# HV_Stage.net
KiCad netlist of a schematic drawn in Altium Designer
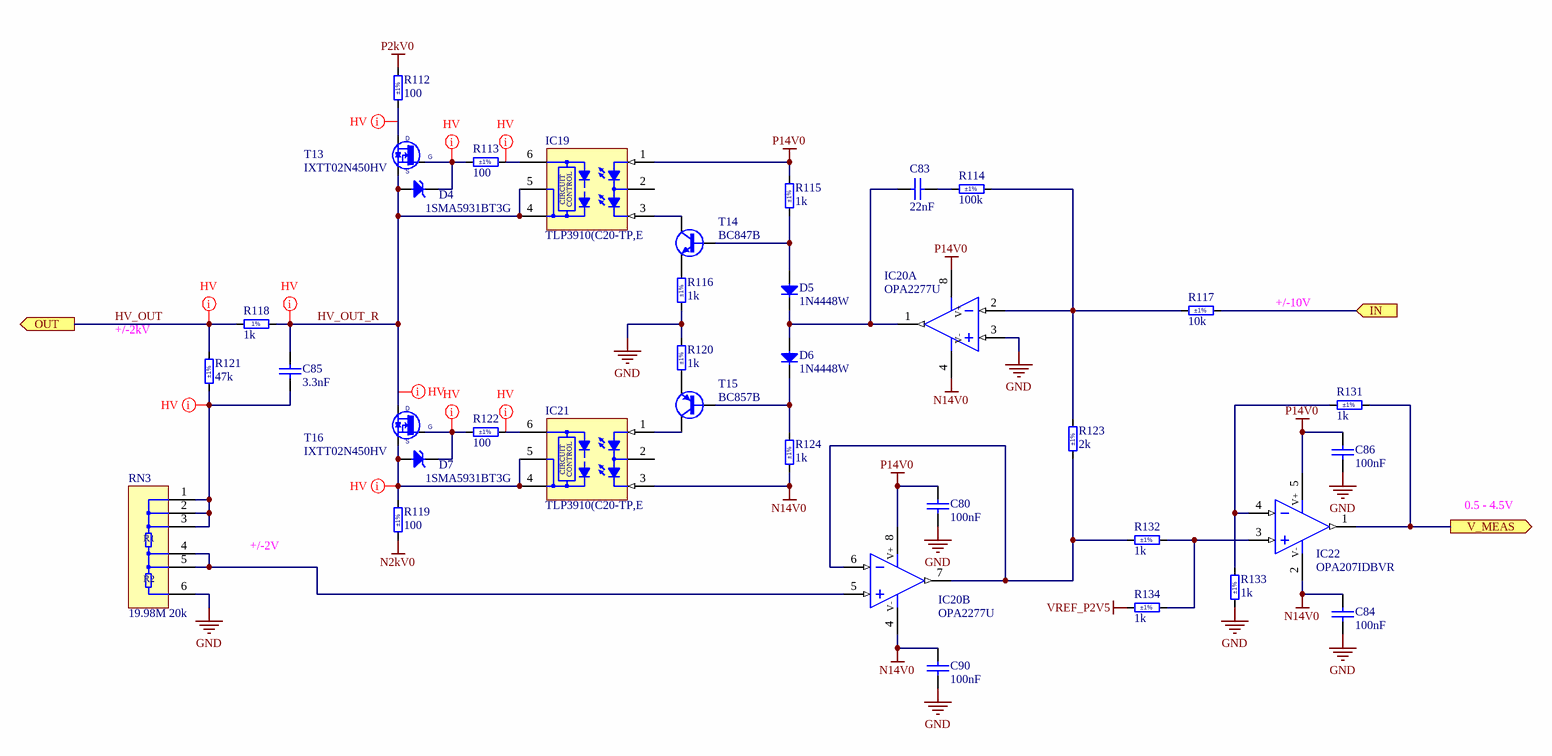
[diagram p0: HV_Stage.SchDoc]

(export (version "E")
  (design (tool "Eeschema 10.0.6"))
  (components
    (comp (ref "C80")
      (value "100nF")
      (footprint "CAPC1005X55N")
      (description "Non-polarised capacitor")
      (fields
        (field (name "PART NUMBER") "CC0402_100NF_50V_10%_X7R")
        (field (name "VOLTAGE") "50V")
        (field (name "AUTHOR") "CERN DEM MR")
      )
      (libsource (lib "Capacitors") (part "Capacitor - non polarized"))
    )
    (comp (ref "C83")
      (value "22nF")
      (footprint "CAPC1005X55N")
      (description "Non-polarised capacitor")
      (fields
        (field (name "PART NUMBER") "CC0402_22NF_50V_5%_X7R")
        (field (name "VOLTAGE") "50V")
        (field (name "AUTHOR") "CERN DEM BC")
      )
      (libsource (lib "Capacitors") (part "Capacitor - non polarized"))
    )
    (comp (ref "C84")
      (value "100nF")
      (footprint "CAPC1005X55N")
      (description "Non-polarised capacitor")
      (fields
        (field (name "PART NUMBER") "CC0402_100NF_50V_10%_X7R")
        (field (name "VOLTAGE") "50V")
        (field (name "AUTHOR") "CERN DEM MR")
      )
      (libsource (lib "Capacitors") (part "Capacitor - non polarized"))
    )
    (comp (ref "C85")
      (value "3.3nF")
      (footprint "CAPC1608X87N")
      (description "Non-polarised capacitor")
      (fields
        (field (name "PART NUMBER") "CC0603_3.3NF_100V_1%_C0G")
        (field (name "VOLTAGE") "100V")
        (field (name "AUTHOR") "CERN DEM HF")
      )
      (libsource (lib "Capacitors") (part "Capacitor - non polarized"))
    )
    (comp (ref "C86")
      (value "100nF")
      (footprint "CAPC1005X55N")
      (description "Non-polarised capacitor")
      (fields
        (field (name "PART NUMBER") "CC0402_100NF_50V_10%_X7R")
        (field (name "VOLTAGE") "50V")
        (field (name "AUTHOR") "CERN DEM MR")
      )
      (libsource (lib "Capacitors") (part "Capacitor - non polarized"))
    )
    (comp (ref "C90")
      (value "100nF")
      (footprint "CAPC1005X55N")
      (description "Non-polarised capacitor")
      (fields
        (field (name "PART NUMBER") "CC0402_100NF_50V_10%_X7R")
        (field (name "VOLTAGE") "50V")
        (field (name "AUTHOR") "CERN DEM MR")
      )
      (libsource (lib "Capacitors") (part "Capacitor - non polarized"))
    )
    (comp (ref "D4")
      (value "1SMA5931BT3G")
      (footprint "DIOM5226X220N")
      (description "Zener Diode")
      (fields
        (field (name "VOLTAGE") "18V")
        (field (name "POWER") "1.5W")
        (field (name "AUTHOR") "CERN DEM BC")
      )
      (libsource (lib "ICs And Semiconductors") (part "Diode Zener"))
    )
    (comp (ref "D5")
      (value "1N4448W")
      (footprint "SOD3715X135N")
      (description "Diode")
      (fields
        (field (name "VOLTAGE") "75V")
        (field (name "POWER") "150mA")
        (field (name "AUTHOR") "CERN DEM JLC")
      )
      (libsource (lib "ICs And Semiconductors") (part "Diode"))
    )
    (comp (ref "D6")
      (value "1N4448W")
      (footprint "SOD3715X135N")
      (description "Diode")
      (fields
        (field (name "VOLTAGE") "75V")
        (field (name "POWER") "150mA")
        (field (name "AUTHOR") "CERN DEM JLC")
      )
      (libsource (lib "ICs And Semiconductors") (part "Diode"))
    )
    (comp (ref "D7")
      (value "1SMA5931BT3G")
      (footprint "DIOM5226X220N")
      (description "Zener Diode")
      (fields
        (field (name "VOLTAGE") "18V")
        (field (name "POWER") "1.5W")
        (field (name "AUTHOR") "CERN DEM BC")
      )
      (libsource (lib "ICs And Semiconductors") (part "Diode Zener"))
    )
    (comp (ref "IC19")
      (value "TLP3910(C20-TP,E")
      (footprint "TOSHIBA_SOIC127P1000X220-6N")
      (description "Optoisolator Photovoltaic Output 5000Vrms 2 Channel")
      (fields (field (name "MANUFACTURER") "TOSHIBA") (field (name "AUTHOR") "CERN DEM HF"))
      (libsource (lib "ICs And Semiconductors") (part "TLP3910"))
    )
    (comp (ref "IC20")
      (value "OPA2277U")
      (footprint "SOIC127P600X175-8N")
      (description "Dual Operational Amplifier")
      (fields (field (name "MANUFACTURER") "TEXAS INSTRUMENTS") (field (name "AUTHOR") "CERN DEM BC"))
      (libsource (lib "ICs And Semiconductors") (part "Operational Amplifier x2 Type1"))
    )
    (comp (ref "IC21")
      (value "TLP3910(C20-TP,E")
      (footprint "TOSHIBA_SOIC127P1000X220-6N")
      (description "Optoisolator Photovoltaic Output 5000Vrms 2 Channel")
      (fields (field (name "MANUFACTURER") "TOSHIBA") (field (name "AUTHOR") "CERN DEM HF"))
      (libsource (lib "ICs And Semiconductors") (part "TLP3910"))
    )
    (comp (ref "IC22")
      (value "OPA207IDBVR")
      (footprint "SOT95P280X145-5N")
      (description "2.2nV/sqrt Hz, Low-Power, 36-V Operational Amplifier")
      (fields (field (name "MANUFACTURER") "TEXAS INSTRUMENTS"))
      (libsource (lib "Operational Amplifiers") (part "OPA207IDBVR"))
    )
    (comp (ref "R112")
      (value "100")
      (footprint "RESC2012X60N")
      (description "Resistor - 1%")
      (fields
        (field (name "TOLERANCE") "±1%")
        (field (name "PART NUMBER") "R0805_100R_1%_0.125W_100PPM")
        (field (name "POWER") "0.125W")
        (field (name "AUTHOR") "CERN DEM JLC")
      )
      (libsource (lib "Resistors") (part "Resistor - 1%"))
    )
    (comp (ref "R113")
      (value "100")
      (footprint "RESC2012X60N")
      (description "Resistor - 1%")
      (fields
        (field (name "TOLERANCE") "±1%")
        (field (name "PART NUMBER") "R0805_100R_1%_0.125W_100PPM")
        (field (name "POWER") "0.125W")
        (field (name "AUTHOR") "CERN DEM JLC")
      )
      (libsource (lib "Resistors") (part "Resistor - 1%"))
    )
    (comp (ref "R114")
      (value "100k")
      (footprint "RESC1005X40N")
      (description "Resistor - 1%")
      (fields
        (field (name "TOLERANCE") "±1%")
        (field (name "PART NUMBER") "R0402_100K_1%_0.0625W_100PPM")
        (field (name "POWER") "0.0625W")
        (field (name "AUTHOR") "CERN DEM JLC")
      )
      (libsource (lib "Resistors") (part "Resistor - 1%"))
    )
    (comp (ref "R115")
      (value "1k")
      (footprint "RESC1005X40N")
      (description "Resistor - 1%")
      (fields
        (field (name "TOLERANCE") "±1%")
        (field (name "PART NUMBER") "R0402_1K_1%_0.0625W_100PPM")
        (field (name "POWER") "0.0625W")
        (field (name "AUTHOR") "CERN DEM JLC")
      )
      (libsource (lib "Resistors") (part "Resistor - 1%"))
    )
    (comp (ref "R116")
      (value "1k")
      (footprint "RESC1005X40N")
      (description "Resistor - 1%")
      (fields
        (field (name "TOLERANCE") "±1%")
        (field (name "PART NUMBER") "R0402_1K_1%_0.0625W_100PPM")
        (field (name "POWER") "0.0625W")
        (field (name "AUTHOR") "CERN DEM JLC")
      )
      (libsource (lib "Resistors") (part "Resistor - 1%"))
    )
    (comp (ref "R117")
      (value "10k")
      (footprint "RESC1005X40N")
      (description "Resistor - 1%")
      (fields
        (field (name "TOLERANCE") "±1%")
        (field (name "PART NUMBER") "R0402_10K_1%_0.0625W_100PPM")
        (field (name "POWER") "0.0625W")
        (field (name "AUTHOR") "CERN DEM JLC")
      )
      (libsource (lib "Resistors") (part "Resistor - 1%"))
    )
    (comp (ref "R118")
      (value "1k")
      (footprint "RESC6331X70N")
      (description "CRMV2512AF 1K 1% 100 Ef E3")
      (fields
        (field (name "MANUFACTURER") "Vishay")
        (field (name "MANUFACTURER PART NUMBER") "CRMV2512AF1K00FKEF")
      )
      (libsource (lib "mb") (part "CRMV2512AF1K00FKEF"))
    )
    (comp (ref "R119")
      (value "100")
      (footprint "RESC2012X60N")
      (description "Resistor - 1%")
      (fields
        (field (name "TOLERANCE") "±1%")
        (field (name "PART NUMBER") "R0805_100R_1%_0.125W_100PPM")
        (field (name "POWER") "0.125W")
        (field (name "AUTHOR") "CERN DEM JLC")
      )
      (libsource (lib "Resistors") (part "Resistor - 1%"))
    )
    (comp (ref "R120")
      (value "1k")
      (footprint "RESC1005X40N")
      (description "Resistor - 1%")
      (fields
        (field (name "TOLERANCE") "±1%")
        (field (name "PART NUMBER") "R0402_1K_1%_0.0625W_100PPM")
        (field (name "POWER") "0.0625W")
        (field (name "AUTHOR") "CERN DEM JLC")
      )
      (libsource (lib "Resistors") (part "Resistor - 1%"))
    )
    (comp (ref "R121")
      (value "47k")
      (footprint "RESC2012X60N")
      (description "Resistor - 1%")
      (fields
        (field (name "TOLERANCE") "±1%")
        (field (name "PART NUMBER") "R0805_47K_1%_0.125W_100PPM")
        (field (name "POWER") "0.125W")
        (field (name "AUTHOR") "CERN DEM JLC")
      )
      (libsource (lib "Resistors") (part "Resistor - 1%"))
    )
    (comp (ref "R122")
      (value "100")
      (footprint "RESC2012X60N")
      (description "Resistor - 1%")
      (fields
        (field (name "TOLERANCE") "±1%")
        (field (name "PART NUMBER") "R0805_100R_1%_0.125W_100PPM")
        (field (name "POWER") "0.125W")
        (field (name "AUTHOR") "CERN DEM JLC")
      )
      (libsource (lib "Resistors") (part "Resistor - 1%"))
    )
    (comp (ref "R123")
      (value "2k")
      (footprint "RESC1005X40N")
      (description "Resistor - 1%")
      (fields
        (field (name "TOLERANCE") "±1%")
        (field (name "PART NUMBER") "R0402_2K_1%_0.0625W_100PPM")
        (field (name "POWER") "0.0625W")
        (field (name "AUTHOR") "CERN DEM JLC")
      )
      (libsource (lib "Resistors") (part "Resistor - 1%"))
    )
    (comp (ref "R124")
      (value "1k")
      (footprint "RESC1005X40N")
      (description "Resistor - 1%")
      (fields
        (field (name "TOLERANCE") "±1%")
        (field (name "PART NUMBER") "R0402_1K_1%_0.0625W_100PPM")
        (field (name "POWER") "0.0625W")
        (field (name "AUTHOR") "CERN DEM JLC")
      )
      (libsource (lib "Resistors") (part "Resistor - 1%"))
    )
    (comp (ref "R131")
      (value "1k")
      (footprint "RESC1005X40N")
      (description "Resistor - 1%")
      (fields
        (field (name "TOLERANCE") "±1%")
        (field (name "PART NUMBER") "R0402_1K_1%_0.0625W_100PPM")
        (field (name "POWER") "0.0625W")
        (field (name "AUTHOR") "CERN DEM JLC")
      )
      (libsource (lib "Resistors") (part "Resistor - 1%"))
    )
    (comp (ref "R132")
      (value "1k")
      (footprint "RESC1005X40N")
      (description "Resistor - 1%")
      (fields
        (field (name "TOLERANCE") "±1%")
        (field (name "PART NUMBER") "R0402_1K_1%_0.0625W_100PPM")
        (field (name "POWER") "0.0625W")
        (field (name "AUTHOR") "CERN DEM JLC")
      )
      (libsource (lib "Resistors") (part "Resistor - 1%"))
    )
    (comp (ref "R133")
      (value "1k")
      (footprint "RESC1005X40N")
      (description "Resistor - 1%")
      (fields
        (field (name "TOLERANCE") "±1%")
        (field (name "PART NUMBER") "R0402_1K_1%_0.0625W_100PPM")
        (field (name "POWER") "0.0625W")
        (field (name "AUTHOR") "CERN DEM JLC")
      )
      (libsource (lib "Resistors") (part "Resistor - 1%"))
    )
    (comp (ref "R134")
      (value "1k")
      (footprint "RESC1005X40N")
      (description "Resistor - 1%")
      (fields
        (field (name "TOLERANCE") "±1%")
        (field (name "PART NUMBER") "R0402_1K_1%_0.0625W_100PPM")
        (field (name "POWER") "0.0625W")
        (field (name "AUTHOR") "CERN DEM JLC")
      )
      (libsource (lib "Resistors") (part "Resistor - 1%"))
    )
    (comp (ref "RN3")
      (value "19.98M 20k")
      (footprint "RN_CADDOCK_HVD5_vertical")
      (description "Ultra-Precision Voltage Dividers HVD Series")
      (fields
        (field (name "PART NUMBER") "RN_19.98M_20K_CADDOCK_HVD5-A20M-050-05")
        (field (name "POWER") "31mW")
        (field (name "AUTHOR") "CERN DEM HF")
      )
      (libsource (lib "mb") (part "CADDOCK_HVD5-A20M-050-05"))
    )
    (comp (ref "T13")
      (value "IXTT02N450HV")
      (footprint "IXYS_TO-268AA (D3Pak-HV)")
      (description "MOSFET N-CH 4500V 0.2A TO268")
      (fields (field (name "MANUFACTURER") "IXYS"))
      (libsource (lib "mb") (part "IXTT02N450HV"))
    )
    (comp (ref "T14")
      (value "BC847B")
      (footprint "SOT95P230X110-3N")
      (description "NPN Transistor")
      (fields (field (name "MANUFACTURER") "NXP SEMICONDUCTORS") (field (name "AUTHOR") "CERN DEM JLC"))
      (libsource (lib "ICs And Semiconductors") (part "NPN B1 E2 C3"))
    )
    (comp (ref "T15")
      (value "BC857B")
      (footprint "SOT95P230X110-3N")
      (description "PNP Transistor")
      (fields (field (name "MANUFACTURER") "NXP SEMICONDUCTORS") (field (name "AUTHOR") "CERN DEM JLC"))
      (libsource (lib "ICs And Semiconductors") (part "PNP B1 E2 C3"))
    )
    (comp (ref "T16")
      (value "IXTT02N450HV")
      (footprint "IXYS_TO-268AA (D3Pak-HV)")
      (description "MOSFET N-CH 4500V 0.2A TO268")
      (fields (field (name "MANUFACTURER") "IXYS"))
      (libsource (lib "mb") (part "IXTT02N450HV"))
    )
  )
  (nets
    (net (code "1") (name "/HV_OUT") (class "Default")
      (node (ref "R118") (pin "1") (pinfunction "1_1") (pintype "passive"))
      (node (ref "R121") (pin "2") (pinfunction "2_2") (pintype "passive"))
    )
    (net (code "2") (name "/HV_OUT_R") (class "Default")
      (node (ref "C85") (pin "2") (pinfunction "2_2") (pintype "passive"))
      (node (ref "D4") (pin "2") (pinfunction "A_2") (pintype "passive"))
      (node (ref "IC19") (pin "4") (pinfunction "K_4") (pintype "passive"))
      (node (ref "IC19") (pin "5") (pinfunction "K_5") (pintype "passive"))
      (node (ref "R118") (pin "2") (pinfunction "2_2") (pintype "passive"))
      (node (ref "T13") (pin "2") (pinfunction "S_2") (pintype "passive"))
      (node (ref "T16") (pin "3") (pinfunction "D_3") (pintype "passive"))
    )
    (net (code "3") (name "/IN") (class "Default")
      (node (ref "R117") (pin "2") (pinfunction "2_2") (pintype "passive"))
    )
    (net (code "4") (name "/V_MEAS") (class "Default")
      (node (ref "IC22") (pin "1") (pinfunction "OUT_1") (pintype "output"))
      (node (ref "R131") (pin "1") (pinfunction "1_1") (pintype "passive"))
    )
    (net (code "5") (name "GND") (class "Default")
      (node (ref "C80") (pin "1") (pinfunction "1_1") (pintype "passive"))
      (node (ref "C84") (pin "1") (pinfunction "1_1") (pintype "passive"))
      (node (ref "C86") (pin "1") (pinfunction "1_1") (pintype "passive"))
      (node (ref "C90") (pin "1") (pinfunction "1_1") (pintype "passive"))
      (node (ref "IC20") (pin "3") (pinfunction "IN+_3") (pintype "input"))
      (node (ref "R116") (pin "1") (pinfunction "1_1") (pintype "passive"))
      (node (ref "R120") (pin "2") (pinfunction "2_2") (pintype "passive"))
      (node (ref "R133") (pin "2") (pinfunction "2_2") (pintype "passive"))
      (node (ref "RN3") (pin "6") (pinfunction "6_6") (pintype "power_in"))
    )
    (net (code "6") (name "N2kV0") (class "Default")
      (node (ref "R119") (pin "2") (pinfunction "2_2") (pintype "passive"))
    )
    (net (code "7") (name "N14V0") (class "Default")
      (node (ref "C84") (pin "2") (pinfunction "2_2") (pintype "passive"))
      (node (ref "C90") (pin "2") (pinfunction "2_2") (pintype "passive"))
      (node (ref "IC20") (pin "4") (pinfunction "V-_4") (pintype "power_in"))
      (node (ref "IC21") (pin "3") (pinfunction "K_3") (pintype "input"))
      (node (ref "IC22") (pin "2") (pinfunction "V-_2") (pintype "power_in"))
      (node (ref "R124") (pin "1") (pinfunction "1_1") (pintype "passive"))
    )
    (net (code "8") (name "Net-(C83-Pad2)") (class "Default")
      (node (ref "C83") (pin "2") (pinfunction "2_2") (pintype "passive"))
      (node (ref "R114") (pin "1") (pinfunction "1_1") (pintype "passive"))
    )
    (net (code "9") (name "Net-(C85-Pad1)") (class "Default")
      (node (ref "C85") (pin "1") (pinfunction "1_1") (pintype "passive"))
      (node (ref "R121") (pin "1") (pinfunction "1_1") (pintype "passive"))
      (node (ref "RN3") (pin "1") (pinfunction "1_1") (pintype "power_in"))
      (node (ref "RN3") (pin "2") (pinfunction "2_2") (pintype "passive"))
      (node (ref "RN3") (pin "3") (pinfunction "3_3") (pintype "passive"))
    )
    (net (code "10") (name "Net-(D4-C)") (class "Default")
      (node (ref "D4") (pin "1") (pinfunction "C_1") (pintype "passive"))
      (node (ref "R113") (pin "2") (pinfunction "2_2") (pintype "passive"))
      (node (ref "T13") (pin "1") (pinfunction "G_1") (pintype "passive"))
    )
    (net (code "11") (name "Net-(D5-A)") (class "Default")
      (node (ref "D5") (pin "2") (pinfunction "A_2") (pintype "passive"))
      (node (ref "R115") (pin "1") (pinfunction "1_1") (pintype "passive"))
      (node (ref "T14") (pin "1") (pinfunction "B_1") (pintype "passive"))
    )
    (net (code "12") (name "Net-(D5-C)") (class "Default")
      (node (ref "C83") (pin "1") (pinfunction "1_1") (pintype "passive"))
      (node (ref "D5") (pin "1") (pinfunction "C_1") (pintype "passive"))
      (node (ref "D6") (pin "2") (pinfunction "A_2") (pintype "passive"))
      (node (ref "IC20") (pin "1") (pinfunction "OUT_1") (pintype "output"))
    )
    (net (code "13") (name "Net-(D6-C)") (class "Default")
      (node (ref "D6") (pin "1") (pinfunction "C_1") (pintype "passive"))
      (node (ref "R124") (pin "2") (pinfunction "2_2") (pintype "passive"))
      (node (ref "T15") (pin "1") (pinfunction "B_1") (pintype "passive"))
    )
    (net (code "14") (name "Net-(D7-A)") (class "Default")
      (node (ref "D7") (pin "2") (pinfunction "A_2") (pintype "passive"))
      (node (ref "IC21") (pin "4") (pinfunction "K_4") (pintype "passive"))
      (node (ref "IC21") (pin "5") (pinfunction "K_5") (pintype "passive"))
      (node (ref "R119") (pin "1") (pinfunction "1_1") (pintype "passive"))
      (node (ref "T16") (pin "2") (pinfunction "S_2") (pintype "passive"))
    )
    (net (code "15") (name "Net-(D7-C)") (class "Default")
      (node (ref "D7") (pin "1") (pinfunction "C_1") (pintype "passive"))
      (node (ref "R122") (pin "1") (pinfunction "1_1") (pintype "passive"))
      (node (ref "T16") (pin "1") (pinfunction "G_1") (pintype "passive"))
    )
    (net (code "16") (name "Net-(IC19-A-Pad6)") (class "Default")
      (node (ref "IC19") (pin "6") (pinfunction "A_6") (pintype "passive"))
      (node (ref "R113") (pin "1") (pinfunction "1_1") (pintype "passive"))
    )
    (net (code "17") (name "Net-(IC20A-IN-)") (class "Default")
      (node (ref "IC20") (pin "2") (pinfunction "IN-_2") (pintype "input"))
      (node (ref "R114") (pin "2") (pinfunction "2_2") (pintype "passive"))
      (node (ref "R117") (pin "1") (pinfunction "1_1") (pintype "passive"))
      (node (ref "R123") (pin "2") (pinfunction "2_2") (pintype "passive"))
    )
    (net (code "18") (name "Net-(IC20B-IN+)") (class "Default")
      (node (ref "IC20") (pin "5") (pinfunction "IN+_5") (pintype "input"))
      (node (ref "RN3") (pin "4") (pinfunction "4_4") (pintype "passive"))
      (node (ref "RN3") (pin "5") (pinfunction "5_5") (pintype "passive"))
    )
    (net (code "19") (name "Net-(IC20B-IN-)") (class "Default")
      (node (ref "IC20") (pin "6") (pinfunction "IN-_6") (pintype "input"))
      (node (ref "IC20") (pin "7") (pinfunction "OUT_7") (pintype "output"))
      (node (ref "R123") (pin "1") (pinfunction "1_1") (pintype "passive"))
      (node (ref "R132") (pin "2") (pinfunction "2_2") (pintype "passive"))
    )
    (net (code "20") (name "Net-(IC21-A-Pad6)") (class "Default")
      (node (ref "IC21") (pin "6") (pinfunction "A_6") (pintype "passive"))
      (node (ref "R122") (pin "2") (pinfunction "2_2") (pintype "passive"))
    )
    (net (code "21") (name "Net-(IC22-IN+)") (class "Default")
      (node (ref "IC22") (pin "3") (pinfunction "IN+_3") (pintype "input"))
      (node (ref "R132") (pin "1") (pinfunction "1_1") (pintype "passive"))
      (node (ref "R134") (pin "1") (pinfunction "1_1") (pintype "passive"))
    )
    (net (code "22") (name "Net-(IC22-IN-)") (class "Default")
      (node (ref "IC22") (pin "4") (pinfunction "IN-_4") (pintype "input"))
      (node (ref "R131") (pin "2") (pinfunction "2_2") (pintype "passive"))
      (node (ref "R133") (pin "1") (pinfunction "1_1") (pintype "passive"))
    )
    (net (code "23") (name "Net-(T13-D)") (class "Default")
      (node (ref "R112") (pin "1") (pinfunction "1_1") (pintype "passive"))
      (node (ref "T13") (pin "3") (pinfunction "D_3") (pintype "passive"))
    )
    (net (code "24") (name "Net-(T14-C)") (class "Default")
      (node (ref "IC19") (pin "3") (pinfunction "K_3") (pintype "input"))
      (node (ref "T14") (pin "3") (pinfunction "C_3") (pintype "passive"))
    )
    (net (code "25") (name "Net-(T14-E)") (class "Default")
      (node (ref "R116") (pin "2") (pinfunction "2_2") (pintype "passive"))
      (node (ref "T14") (pin "2") (pinfunction "E_2") (pintype "passive"))
    )
    (net (code "26") (name "Net-(T15-C)") (class "Default")
      (node (ref "IC21") (pin "1") (pinfunction "A_1") (pintype "input"))
      (node (ref "T15") (pin "3") (pinfunction "C_3") (pintype "passive"))
    )
    (net (code "27") (name "Net-(T15-E)") (class "Default")
      (node (ref "R120") (pin "1") (pinfunction "1_1") (pintype "passive"))
      (node (ref "T15") (pin "2") (pinfunction "E_2") (pintype "passive"))
    )
    (net (code "28") (name "P2kV0") (class "Default")
      (node (ref "R112") (pin "2") (pinfunction "2_2") (pintype "passive"))
    )
    (net (code "29") (name "P14V0") (class "Default")
      (node (ref "C80") (pin "2") (pinfunction "2_2") (pintype "passive"))
      (node (ref "C86") (pin "2") (pinfunction "2_2") (pintype "passive"))
      (node (ref "IC19") (pin "1") (pinfunction "A_1") (pintype "input"))
      (node (ref "IC20") (pin "8") (pinfunction "V+_8") (pintype "power_in"))
      (node (ref "IC22") (pin "5") (pinfunction "V+_5") (pintype "power_in"))
      (node (ref "R115") (pin "2") (pinfunction "2_2") (pintype "passive"))
    )
    (net (code "30") (name "VREF_P2V5") (class "Default")
      (node (ref "R134") (pin "2") (pinfunction "2_2") (pintype "passive"))
    )
    (net (code "31") (name "unconnected-(IC19-NC-Pad2)") (class "Default")
      (node (ref "IC19") (pin "2") (pinfunction "NC_2") (pintype "passive"))
    )
    (net (code "32") (name "unconnected-(IC21-NC-Pad2)") (class "Default")
      (node (ref "IC21") (pin "2") (pinfunction "NC_2") (pintype "passive"))
    )
  )
)
